# controlBoard-0_5.net
KiCad netlist of a schematic drawn in EAGLE
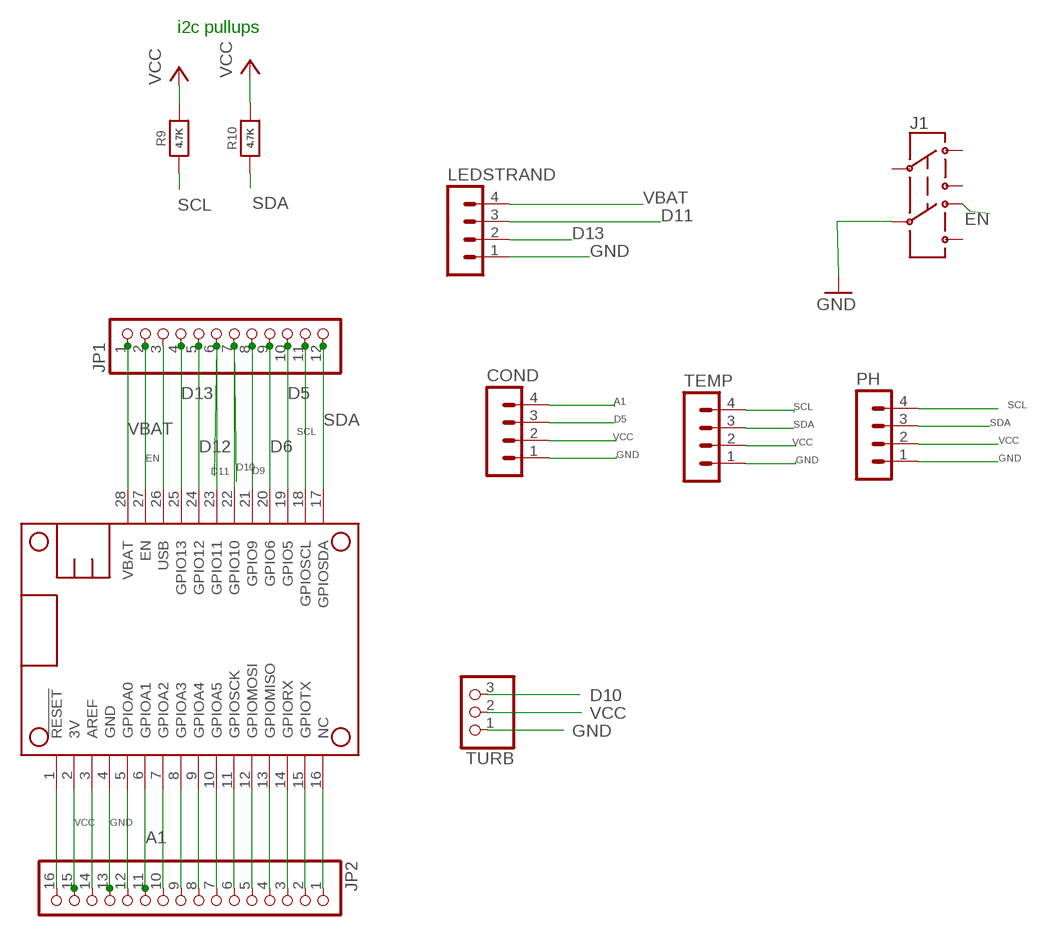
[diagram p0: schematic, sheet 1]

(export (version "E")
  (design (tool "Eeschema 10.0.6"))
  (components
    (comp (ref "COND")
      (value "MA04-1")
      (footprint "eagle-import:MA04-1")
      (libsource (lib "eagle-import") (part "MA04-1"))
    )
    (comp (ref "J1")
      (value "AYZ0202")
      (footprint "eagle-import:AYZ0202")
      (libsource (lib "eagle-import") (part "AYZ0202"))
    )
    (comp (ref "JP1")
      (value "PINHD-1X12")
      (footprint "eagle-import:1X12")
      (libsource (lib "eagle-import") (part "PINHD-1X12"))
    )
    (comp (ref "JP2")
      (value "PINHD-1X16")
      (footprint "eagle-import:1X16")
      (libsource (lib "eagle-import") (part "PINHD-1X16"))
    )
    (comp (ref "LEDSTRAND")
      (value "MA04-1")
      (footprint "eagle-import:MA04-1")
      (libsource (lib "eagle-import") (part "MA04-1"))
    )
    (comp (ref "MS1")
      (value "FEATHERWING")
      (footprint "eagle-import:FEATHERWING")
      (libsource (lib "eagle-import") (part "FEATHERWING"))
    )
    (comp (ref "PH")
      (value "MA04-1")
      (footprint "eagle-import:MA04-1")
      (fields (field (name "OC_FARNELL") "unknown") (field (name "OC_NEWARK") "unknown"))
      (libsource (lib "eagle-import") (part "MA04-1"))
    )
    (comp (ref "R9")
      (value "4.7K")
      (footprint "eagle-import:0603-NO")
      (libsource (lib "eagle-import") (part "RESISTOR_0603_NOOUT"))
    )
    (comp (ref "R10")
      (value "4.7K")
      (footprint "eagle-import:0603-NO")
      (libsource (lib "eagle-import") (part "RESISTOR_0603_NOOUT"))
    )
    (comp (ref "TEMP")
      (value "MA04-1")
      (footprint "eagle-import:MA04-1")
      (libsource (lib "eagle-import") (part "MA04-1"))
    )
    (comp (ref "TURB")
      (value "PINHD-1X3")
      (footprint "eagle-import:1X03")
      (libsource (lib "eagle-import") (part "PINHD-1X3"))
    )
  )
  (nets
    (net (code "1") (name "/A1") (class "Default")
      (node (ref "COND") (pin "4") (pinfunction "4_4") (pintype "passive"))
      (node (ref "JP2") (pin "11") (pinfunction "11_11") (pintype "passive"))
      (node (ref "MS1") (pin "6") (pinfunction "GPIOA1_6") (pintype "bidirectional"))
    )
    (net (code "2") (name "/D5") (class "Default")
      (node (ref "COND") (pin "3") (pinfunction "3_3") (pintype "passive"))
      (node (ref "JP1") (pin "10") (pinfunction "10_10") (pintype "passive"))
      (node (ref "MS1") (pin "19") (pinfunction "GPIO5_19") (pintype "bidirectional"))
    )
    (net (code "3") (name "/D6") (class "Default")
      (node (ref "JP1") (pin "9") (pinfunction "9_9") (pintype "passive"))
      (node (ref "MS1") (pin "20") (pinfunction "GPIO6_20") (pintype "bidirectional"))
    )
    (net (code "4") (name "/D9") (class "Default")
      (node (ref "JP1") (pin "8") (pinfunction "8_8") (pintype "passive"))
      (node (ref "MS1") (pin "21") (pinfunction "GPIO9_21") (pintype "bidirectional"))
    )
    (net (code "5") (name "/D10") (class "Default")
      (node (ref "JP1") (pin "7") (pinfunction "7_7") (pintype "passive"))
      (node (ref "MS1") (pin "22") (pinfunction "GPIO10_22") (pintype "bidirectional"))
      (node (ref "TURB") (pin "3") (pinfunction "3_3") (pintype "passive"))
    )
    (net (code "6") (name "/D11") (class "Default")
      (node (ref "JP1") (pin "6") (pinfunction "6_6") (pintype "passive"))
      (node (ref "LEDSTRAND") (pin "3") (pinfunction "3_3") (pintype "passive"))
      (node (ref "MS1") (pin "23") (pinfunction "GPIO11_23") (pintype "bidirectional"))
    )
    (net (code "7") (name "/D12") (class "Default")
      (node (ref "JP1") (pin "5") (pinfunction "5_5") (pintype "passive"))
      (node (ref "MS1") (pin "24") (pinfunction "GPIO12_24") (pintype "bidirectional"))
    )
    (net (code "8") (name "/D13") (class "Default")
      (node (ref "JP1") (pin "4") (pinfunction "4_4") (pintype "passive"))
      (node (ref "LEDSTRAND") (pin "2") (pinfunction "2_2") (pintype "passive"))
      (node (ref "MS1") (pin "25") (pinfunction "GPIO13_25") (pintype "bidirectional"))
    )
    (net (code "9") (name "/EN") (class "Default")
      (node (ref "J1") (pin "6") (pinfunction "4_6") (pintype "bidirectional"))
      (node (ref "JP1") (pin "2") (pinfunction "2_2") (pintype "passive"))
      (node (ref "MS1") (pin "27") (pinfunction "EN_27") (pintype "passive"))
    )
    (net (code "10") (name "/SCL") (class "Default")
      (node (ref "JP1") (pin "11") (pinfunction "11_11") (pintype "passive"))
      (node (ref "MS1") (pin "18") (pinfunction "GPIOSCL_18") (pintype "bidirectional"))
      (node (ref "PH") (pin "4") (pinfunction "4_4") (pintype "passive"))
      (node (ref "R9") (pin "1") (pinfunction "1_1") (pintype "passive"))
      (node (ref "TEMP") (pin "4") (pinfunction "4_4") (pintype "passive"))
    )
    (net (code "11") (name "/SDA") (class "Default")
      (node (ref "JP1") (pin "12") (pinfunction "12_12") (pintype "passive"))
      (node (ref "MS1") (pin "17") (pinfunction "GPIOSDA_17") (pintype "bidirectional"))
      (node (ref "PH") (pin "3") (pinfunction "3_3") (pintype "passive"))
      (node (ref "R10") (pin "1") (pinfunction "1_1") (pintype "passive"))
      (node (ref "TEMP") (pin "3") (pinfunction "3_3") (pintype "passive"))
    )
    (net (code "12") (name "/VBAT") (class "Default")
      (node (ref "JP1") (pin "1") (pinfunction "1_1") (pintype "passive"))
      (node (ref "LEDSTRAND") (pin "4") (pinfunction "4_4") (pintype "passive"))
      (node (ref "MS1") (pin "28") (pinfunction "VBAT_28") (pintype "power_in"))
    )
    (net (code "13") (name "GND") (class "Default")
      (node (ref "COND") (pin "1") (pinfunction "1_1") (pintype "passive"))
      (node (ref "J1") (pin "5") (pinfunction "5_5") (pintype "bidirectional"))
      (node (ref "JP2") (pin "13") (pinfunction "13_13") (pintype "passive"))
      (node (ref "LEDSTRAND") (pin "1") (pinfunction "1_1") (pintype "passive"))
      (node (ref "MS1") (pin "4") (pinfunction "GND_4") (pintype "power_in"))
      (node (ref "PH") (pin "1") (pinfunction "1_1") (pintype "passive"))
      (node (ref "TEMP") (pin "1") (pinfunction "1_1") (pintype "passive"))
      (node (ref "TURB") (pin "1") (pinfunction "1_1") (pintype "passive"))
    )
    (net (code "14") (name "Net-(MS1-AREF)") (class "Default")
      (node (ref "JP2") (pin "14") (pinfunction "14_14") (pintype "passive"))
      (node (ref "MS1") (pin "3") (pinfunction "AREF_3") (pintype "passive"))
    )
    (net (code "15") (name "Net-(MS1-GPIOA0)") (class "Default")
      (node (ref "JP2") (pin "12") (pinfunction "12_12") (pintype "passive"))
      (node (ref "MS1") (pin "5") (pinfunction "GPIOA0_5") (pintype "bidirectional"))
    )
    (net (code "16") (name "Net-(MS1-GPIOA2)") (class "Default")
      (node (ref "JP2") (pin "10") (pinfunction "10_10") (pintype "passive"))
      (node (ref "MS1") (pin "7") (pinfunction "GPIOA2_7") (pintype "bidirectional"))
    )
    (net (code "17") (name "Net-(MS1-GPIOA3)") (class "Default")
      (node (ref "JP2") (pin "9") (pinfunction "9_9") (pintype "passive"))
      (node (ref "MS1") (pin "8") (pinfunction "GPIOA3_8") (pintype "bidirectional"))
    )
    (net (code "18") (name "Net-(MS1-GPIOA4)") (class "Default")
      (node (ref "JP2") (pin "8") (pinfunction "8_8") (pintype "passive"))
      (node (ref "MS1") (pin "9") (pinfunction "GPIOA4_9") (pintype "bidirectional"))
    )
    (net (code "19") (name "Net-(MS1-GPIOA5)") (class "Default")
      (node (ref "JP2") (pin "7") (pinfunction "7_7") (pintype "passive"))
      (node (ref "MS1") (pin "10") (pinfunction "GPIOA5_10") (pintype "bidirectional"))
    )
    (net (code "20") (name "Net-(MS1-GPIOMISO)") (class "Default")
      (node (ref "JP2") (pin "4") (pinfunction "4_4") (pintype "passive"))
      (node (ref "MS1") (pin "13") (pinfunction "GPIOMISO_13") (pintype "bidirectional"))
    )
    (net (code "21") (name "Net-(MS1-GPIOMOSI)") (class "Default")
      (node (ref "JP2") (pin "5") (pinfunction "5_5") (pintype "passive"))
      (node (ref "MS1") (pin "12") (pinfunction "GPIOMOSI_12") (pintype "bidirectional"))
    )
    (net (code "22") (name "Net-(MS1-GPIORX)") (class "Default")
      (node (ref "JP2") (pin "3") (pinfunction "3_3") (pintype "passive"))
      (node (ref "MS1") (pin "14") (pinfunction "GPIORX_14") (pintype "bidirectional"))
    )
    (net (code "23") (name "Net-(MS1-GPIOSCK)") (class "Default")
      (node (ref "JP2") (pin "6") (pinfunction "6_6") (pintype "passive"))
      (node (ref "MS1") (pin "11") (pinfunction "GPIOSCK_11") (pintype "bidirectional"))
    )
    (net (code "24") (name "Net-(MS1-GPIOTX)") (class "Default")
      (node (ref "JP2") (pin "2") (pinfunction "2_2") (pintype "passive"))
      (node (ref "MS1") (pin "15") (pinfunction "GPIOTX_15") (pintype "bidirectional"))
    )
    (net (code "25") (name "Net-(MS1-NC)") (class "Default")
      (node (ref "JP2") (pin "1") (pinfunction "1_1") (pintype "passive"))
      (node (ref "MS1") (pin "16") (pinfunction "NC_16") (pintype "passive"))
    )
    (net (code "26") (name "Net-(MS1-USB)") (class "Default")
      (node (ref "JP1") (pin "3") (pinfunction "3_3") (pintype "passive"))
      (node (ref "MS1") (pin "26") (pinfunction "USB_26") (pintype "power_in"))
    )
    (net (code "27") (name "Net-(MS1-~{RESET})") (class "Default")
      (node (ref "JP2") (pin "16") (pinfunction "16_16") (pintype "passive"))
      (node (ref "MS1") (pin "1") (pinfunction "~{RESET}_1") (pintype "input"))
    )
    (net (code "28") (name "VCC") (class "Default")
      (node (ref "COND") (pin "2") (pinfunction "2_2") (pintype "passive"))
      (node (ref "JP2") (pin "15") (pinfunction "15_15") (pintype "passive"))
      (node (ref "MS1") (pin "2") (pinfunction "3V_2") (pintype "power_in"))
      (node (ref "PH") (pin "2") (pinfunction "2_2") (pintype "passive"))
      (node (ref "R10") (pin "2") (pinfunction "2_2") (pintype "passive"))
      (node (ref "R9") (pin "2") (pinfunction "2_2") (pintype "passive"))
      (node (ref "TEMP") (pin "2") (pinfunction "2_2") (pintype "passive"))
      (node (ref "TURB") (pin "2") (pinfunction "2_2") (pintype "passive"))
    )
    (net (code "29") (name "unconnected-(J1-1-Pad3)") (class "Default")
      (node (ref "J1") (pin "3") (pinfunction "1_3") (pintype "bidirectional"))
    )
    (net (code "30") (name "unconnected-(J1-3-Pad1)") (class "Default")
      (node (ref "J1") (pin "1") (pinfunction "3_1") (pintype "bidirectional"))
    )
    (net (code "31") (name "unconnected-(J1-6-Pad4)") (class "Default")
      (node (ref "J1") (pin "4") (pinfunction "6_4") (pintype "bidirectional"))
    )
    (net (code "32") (name "unconnected-(J1-Pad2)") (class "Default")
      (node (ref "J1") (pin "2") (pinfunction "2_2") (pintype "bidirectional"))
    )
  )
)
